# 06_AMPLIFIER_IQ.net
KiCad netlist of a schematic drawn in Altium Designer
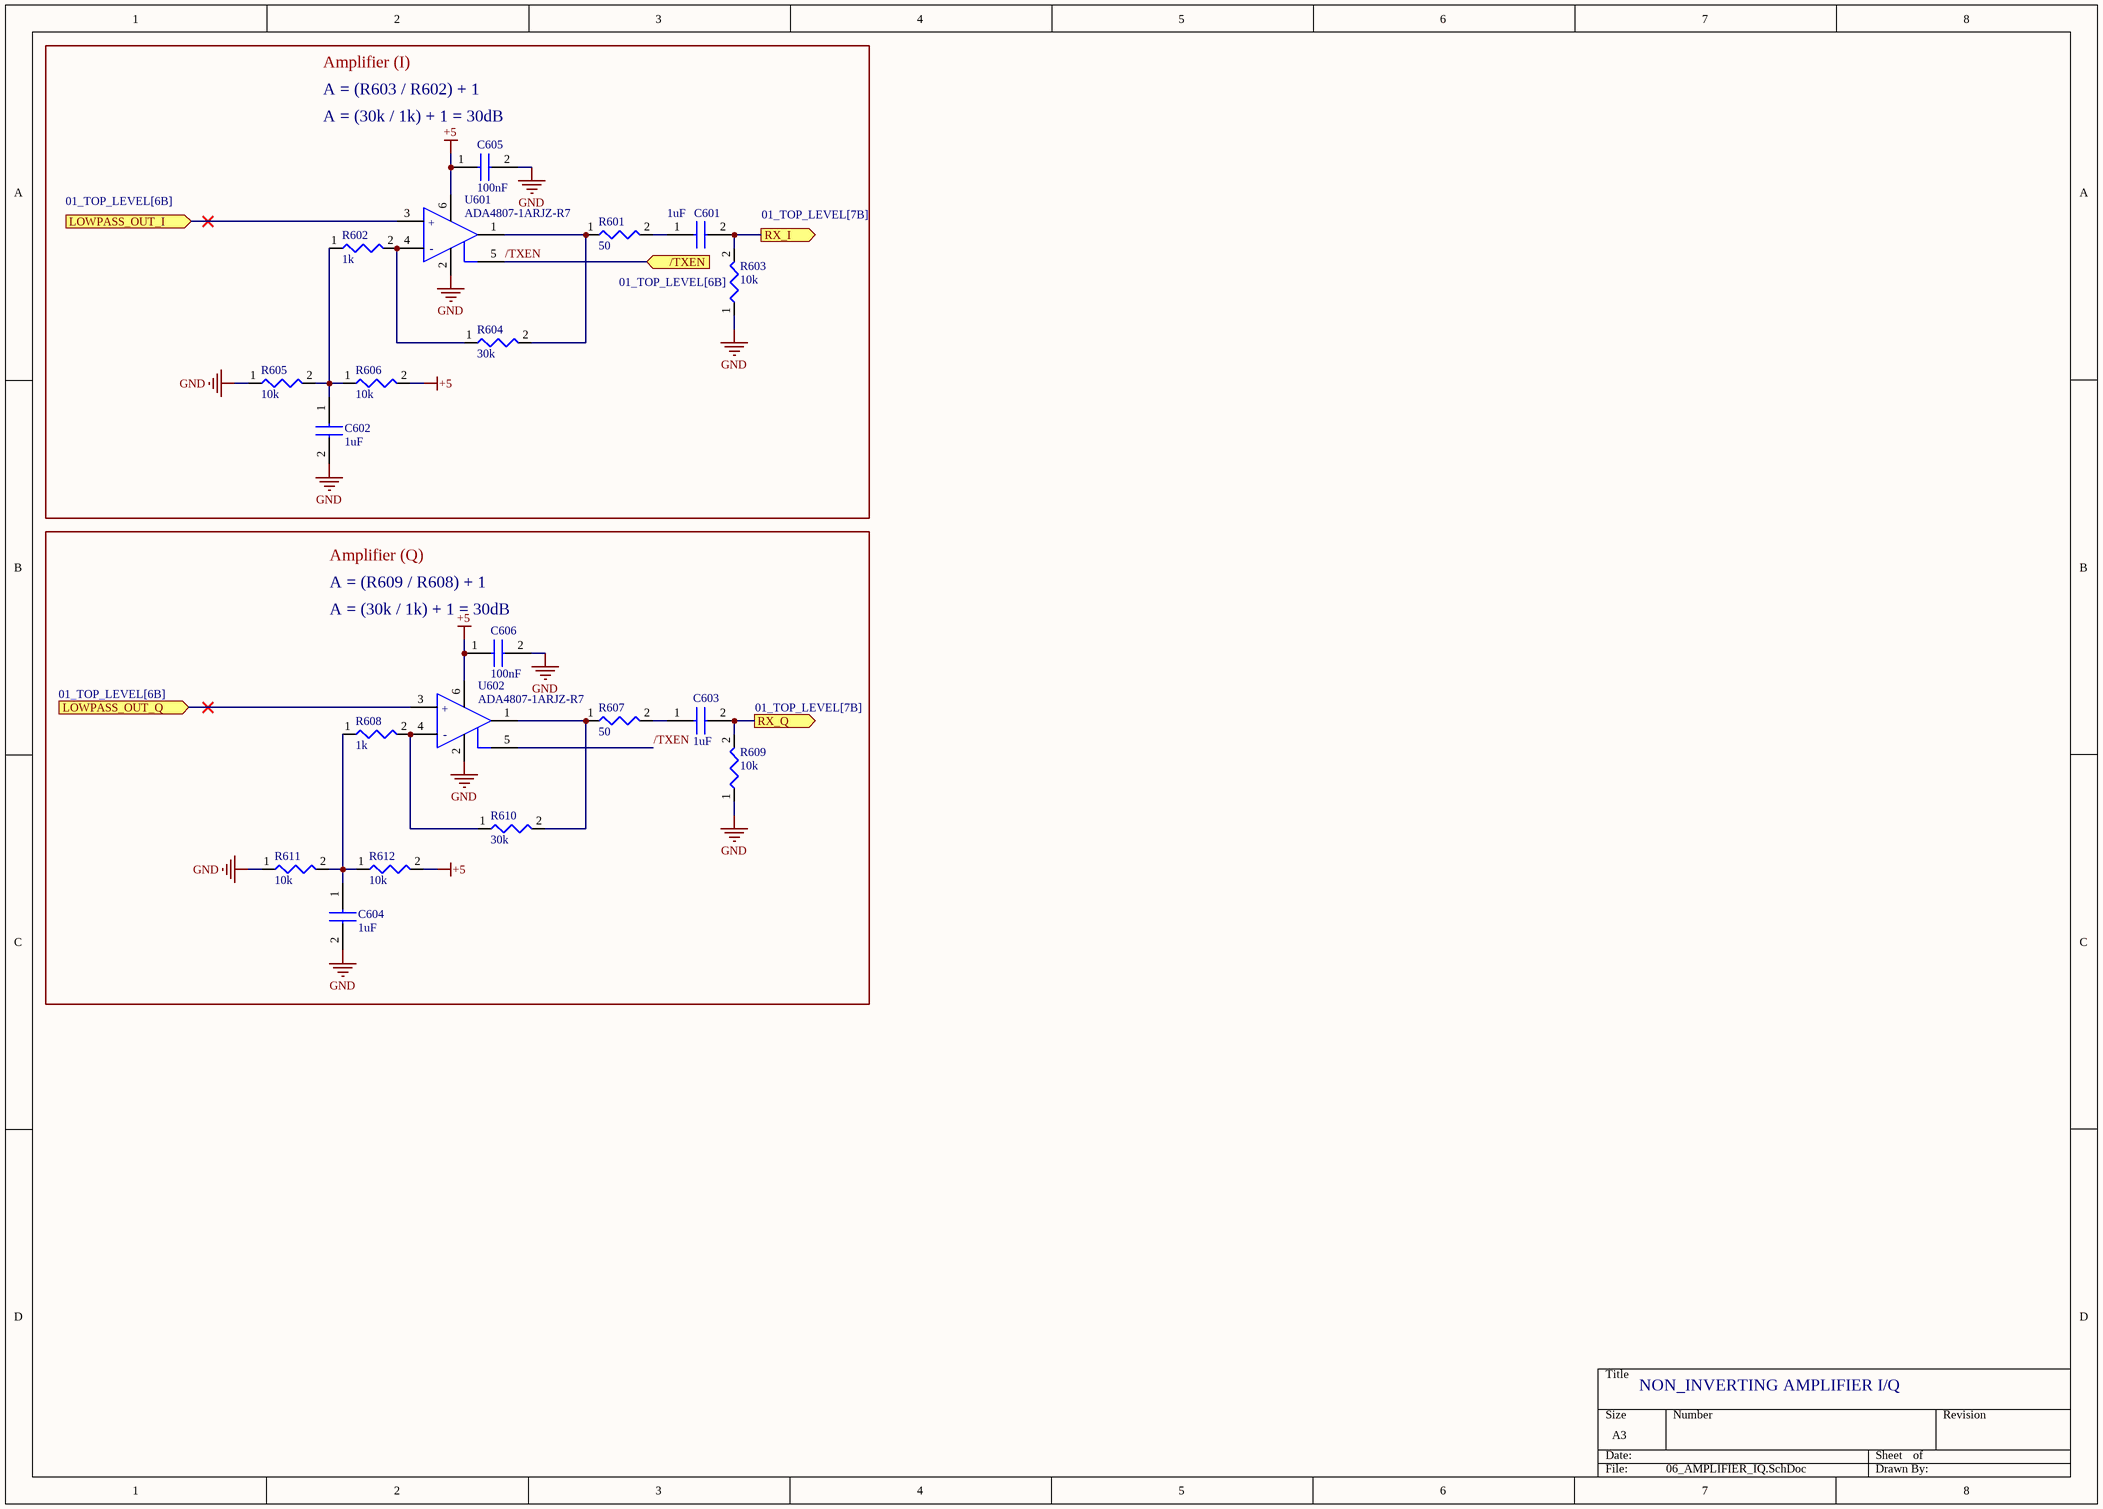
[diagram p0: 06_AMPLIFIER_IQ.SchDoc]

(export (version "E")
  (design (tool "Eeschema 10.0.6"))
  (components
    (comp (ref "C601")
      (value "1uF")
      (footprint "CAP_0805")
      (description "Capacitor SMD 0805")
      (libsource (lib "Passive_Components") (part "CAP_0805"))
    )
    (comp (ref "C602")
      (value "1uF")
      (footprint "CAP_0805")
      (description "Capacitor SMD 0805")
      (libsource (lib "Passive_Components") (part "CAP_0805"))
    )
    (comp (ref "C603")
      (value "1uF")
      (footprint "CAP_0805")
      (description "Capacitor SMD 0805")
      (libsource (lib "Passive_Components") (part "CAP_0805"))
    )
    (comp (ref "C604")
      (value "1uF")
      (footprint "CAP_0805")
      (description "Capacitor SMD 0805")
      (libsource (lib "Passive_Components") (part "CAP_0805"))
    )
    (comp (ref "C605")
      (value "100nF")
      (footprint "CAP_0805")
      (description "Capacitor SMD 0805")
      (libsource (lib "Passive_Components") (part "CAP_0805"))
    )
    (comp (ref "C606")
      (value "100nF")
      (footprint "CAP_0805")
      (description "Capacitor SMD 0805")
      (libsource (lib "Passive_Components") (part "CAP_0805"))
    )
    (comp (ref "R601")
      (value "50")
      (footprint "RES_0805")
      (description "Resistor SMD 0805")
      (libsource (lib "Passive_Components") (part "RES_0805"))
    )
    (comp (ref "R602")
      (value "1k")
      (footprint "RES_0805")
      (description "Resistor SMD 0805")
      (libsource (lib "Passive_Components") (part "RES_0805"))
    )
    (comp (ref "R603")
      (value "10k")
      (footprint "RES_0805")
      (description "Resistor SMD 0805")
      (libsource (lib "Passive_Components") (part "RES_0805"))
    )
    (comp (ref "R604")
      (value "30k")
      (footprint "RES_0805")
      (description "Resistor SMD 0805")
      (libsource (lib "Passive_Components") (part "RES_0805"))
    )
    (comp (ref "R605")
      (value "10k")
      (footprint "RES_0805")
      (description "Resistor SMD 0805")
      (libsource (lib "Passive_Components") (part "RES_0805"))
    )
    (comp (ref "R606")
      (value "10k")
      (footprint "RES_0805")
      (description "Resistor SMD 0805")
      (libsource (lib "Passive_Components") (part "RES_0805"))
    )
    (comp (ref "R607")
      (value "50")
      (footprint "RES_0805")
      (description "Resistor SMD 0805")
      (libsource (lib "Passive_Components") (part "RES_0805"))
    )
    (comp (ref "R608")
      (value "1k")
      (footprint "RES_0805")
      (description "Resistor SMD 0805")
      (libsource (lib "Passive_Components") (part "RES_0805"))
    )
    (comp (ref "R609")
      (value "10k")
      (footprint "RES_0805")
      (description "Resistor SMD 0805")
      (libsource (lib "Passive_Components") (part "RES_0805"))
    )
    (comp (ref "R610")
      (value "30k")
      (footprint "RES_0805")
      (description "Resistor SMD 0805")
      (libsource (lib "Passive_Components") (part "RES_0805"))
    )
    (comp (ref "R611")
      (value "10k")
      (footprint "RES_0805")
      (description "Resistor SMD 0805")
      (libsource (lib "Passive_Components") (part "RES_0805"))
    )
    (comp (ref "R612")
      (value "10k")
      (footprint "RES_0805")
      (description "Resistor SMD 0805")
      (libsource (lib "Passive_Components") (part "RES_0805"))
    )
    (comp (ref "U601")
      (value "ADA4807-1ARJZ-R7")
      (footprint "FP-RJ-6-IPC_A")
      (description "IC OPAMP VFB 1 CIRCUIT SOT23-6")
      (libsource (lib "Altium Content Vault") (part "0cc169e61f44c0172c2773b4ba3b2c6"))
    )
    (comp (ref "U602")
      (value "ADA4807-1ARJZ-R7")
      (footprint "FP-RJ-6-IPC_A")
      (description "IC OPAMP VFB 1 CIRCUIT SOT23-6")
      (libsource (lib "Altium Content Vault") (part "0cc169e61f44c0172c2773b4ba3b2c6"))
    )
  )
  (nets
    (net (code "1") (name "+5") (class "Default")
      (node (ref "C605") (pin "1") (pinfunction "1_1") (pintype "passive"))
      (node (ref "C606") (pin "1") (pinfunction "1_1") (pintype "passive"))
      (node (ref "R606") (pin "2") (pinfunction "2_2") (pintype "passive"))
      (node (ref "R612") (pin "2") (pinfunction "2_2") (pintype "passive"))
      (node (ref "U601") (pin "6") (pinfunction "+VS_6") (pintype "power_in"))
      (node (ref "U602") (pin "6") (pinfunction "+VS_6") (pintype "power_in"))
    )
    (net (code "2") (name "/LOWPASS_OUT_I") (class "Default")
      (node (ref "U601") (pin "3") (pinfunction "+IN_3") (pintype "tri_state"))
    )
    (net (code "3") (name "/LOWPASS_OUT_Q") (class "Default")
      (node (ref "U602") (pin "3") (pinfunction "+IN_3") (pintype "tri_state"))
    )
    (net (code "4") (name "/RX_I") (class "Default")
      (node (ref "C601") (pin "2") (pinfunction "2_2") (pintype "passive"))
      (node (ref "R603") (pin "2") (pinfunction "2_2") (pintype "passive"))
    )
    (net (code "5") (name "/RX_Q") (class "Default")
      (node (ref "C603") (pin "2") (pinfunction "2_2") (pintype "passive"))
      (node (ref "R609") (pin "2") (pinfunction "2_2") (pintype "passive"))
    )
    (net (code "6") (name "/{slash}TXEN") (class "Default")
      (node (ref "U601") (pin "5") (pinfunction "~{DISABLE}_5") (pintype "passive"))
      (node (ref "U602") (pin "5") (pinfunction "~{DISABLE}_5") (pintype "passive"))
    )
    (net (code "7") (name "GND") (class "Default")
      (node (ref "C602") (pin "2") (pinfunction "2_2") (pintype "passive"))
      (node (ref "C604") (pin "2") (pinfunction "2_2") (pintype "passive"))
      (node (ref "C605") (pin "2") (pinfunction "2_2") (pintype "passive"))
      (node (ref "C606") (pin "2") (pinfunction "2_2") (pintype "passive"))
      (node (ref "R603") (pin "1") (pinfunction "1_1") (pintype "passive"))
      (node (ref "R605") (pin "1") (pinfunction "1_1") (pintype "passive"))
      (node (ref "R609") (pin "1") (pinfunction "1_1") (pintype "passive"))
      (node (ref "R611") (pin "1") (pinfunction "1_1") (pintype "passive"))
      (node (ref "U601") (pin "2") (pinfunction "-VS_2") (pintype "power_in"))
      (node (ref "U602") (pin "2") (pinfunction "-VS_2") (pintype "power_in"))
    )
    (net (code "8") (name "Net-(C601-Pad1)") (class "Default")
      (node (ref "C601") (pin "1") (pinfunction "1_1") (pintype "passive"))
      (node (ref "R601") (pin "2") (pinfunction "2_2") (pintype "passive"))
    )
    (net (code "9") (name "Net-(C602-Pad1)") (class "Default")
      (node (ref "C602") (pin "1") (pinfunction "1_1") (pintype "passive"))
      (node (ref "R602") (pin "1") (pinfunction "1_1") (pintype "passive"))
      (node (ref "R605") (pin "2") (pinfunction "2_2") (pintype "passive"))
      (node (ref "R606") (pin "1") (pinfunction "1_1") (pintype "passive"))
    )
    (net (code "10") (name "Net-(C603-Pad1)") (class "Default")
      (node (ref "C603") (pin "1") (pinfunction "1_1") (pintype "passive"))
      (node (ref "R607") (pin "2") (pinfunction "2_2") (pintype "passive"))
    )
    (net (code "11") (name "Net-(C604-Pad1)") (class "Default")
      (node (ref "C604") (pin "1") (pinfunction "1_1") (pintype "passive"))
      (node (ref "R608") (pin "1") (pinfunction "1_1") (pintype "passive"))
      (node (ref "R611") (pin "2") (pinfunction "2_2") (pintype "passive"))
      (node (ref "R612") (pin "1") (pinfunction "1_1") (pintype "passive"))
    )
    (net (code "12") (name "Net-(U601--IN)") (class "Default")
      (node (ref "R602") (pin "2") (pinfunction "2_2") (pintype "passive"))
      (node (ref "R604") (pin "1") (pinfunction "1_1") (pintype "passive"))
      (node (ref "U601") (pin "4") (pinfunction "-IN_4") (pintype "tri_state"))
    )
    (net (code "13") (name "Net-(U601-VOUT)") (class "Default")
      (node (ref "R601") (pin "1") (pinfunction "1_1") (pintype "passive"))
      (node (ref "R604") (pin "2") (pinfunction "2_2") (pintype "passive"))
      (node (ref "U601") (pin "1") (pinfunction "VOUT_1") (pintype "passive"))
    )
    (net (code "14") (name "Net-(U602--IN)") (class "Default")
      (node (ref "R608") (pin "2") (pinfunction "2_2") (pintype "passive"))
      (node (ref "R610") (pin "1") (pinfunction "1_1") (pintype "passive"))
      (node (ref "U602") (pin "4") (pinfunction "-IN_4") (pintype "tri_state"))
    )
    (net (code "15") (name "Net-(U602-VOUT)") (class "Default")
      (node (ref "R607") (pin "1") (pinfunction "1_1") (pintype "passive"))
      (node (ref "R610") (pin "2") (pinfunction "2_2") (pintype "passive"))
      (node (ref "U602") (pin "1") (pinfunction "VOUT_1") (pintype "passive"))
    )
  )
)
